# powerblade_3v3.net
KiCad netlist of a schematic drawn in EAGLE
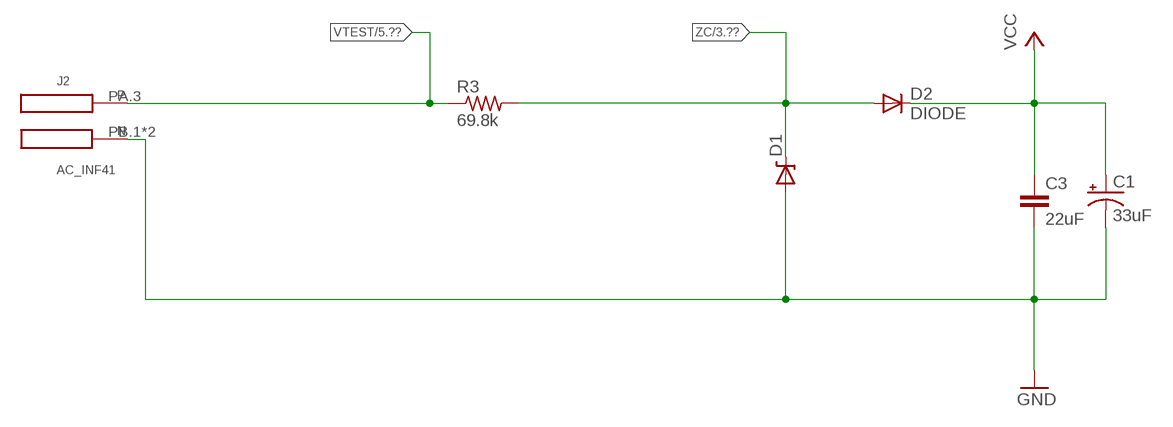
[diagram p0: schematic, sheet 1]
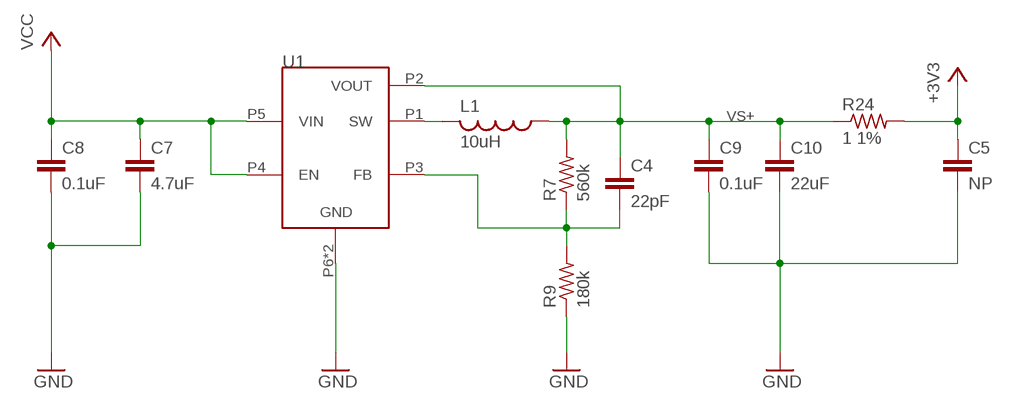
[diagram p1: schematic, sheet 2]
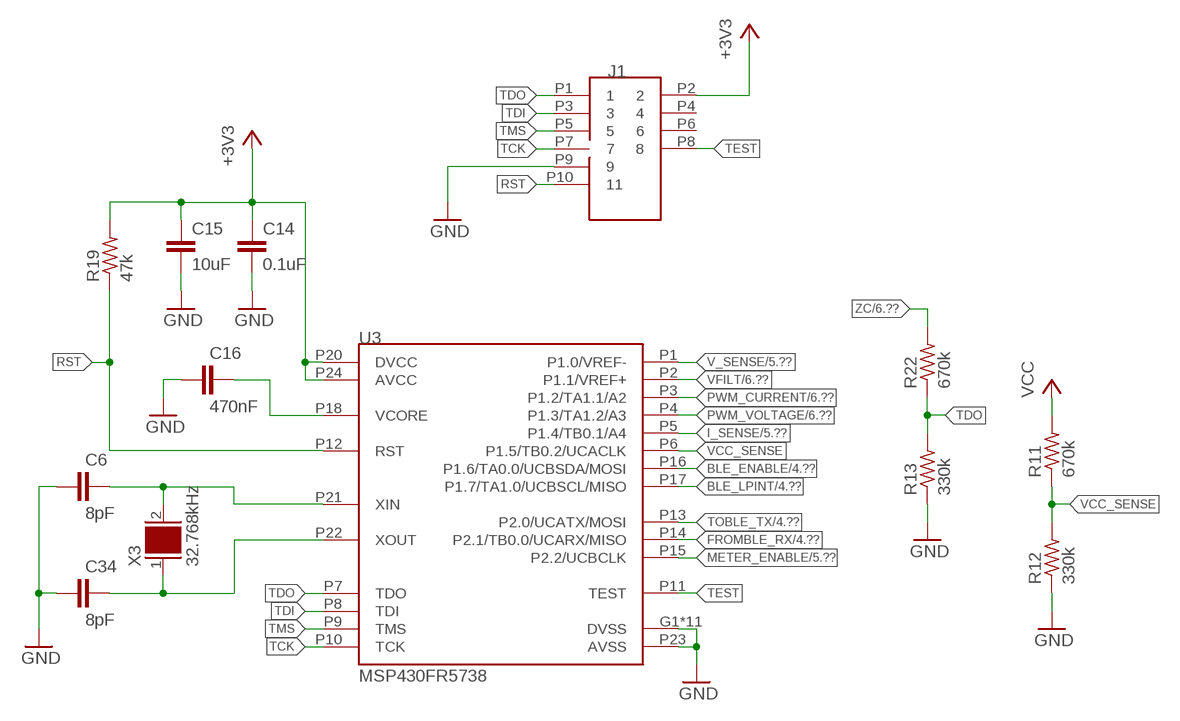
[diagram p2: schematic, sheet 3]
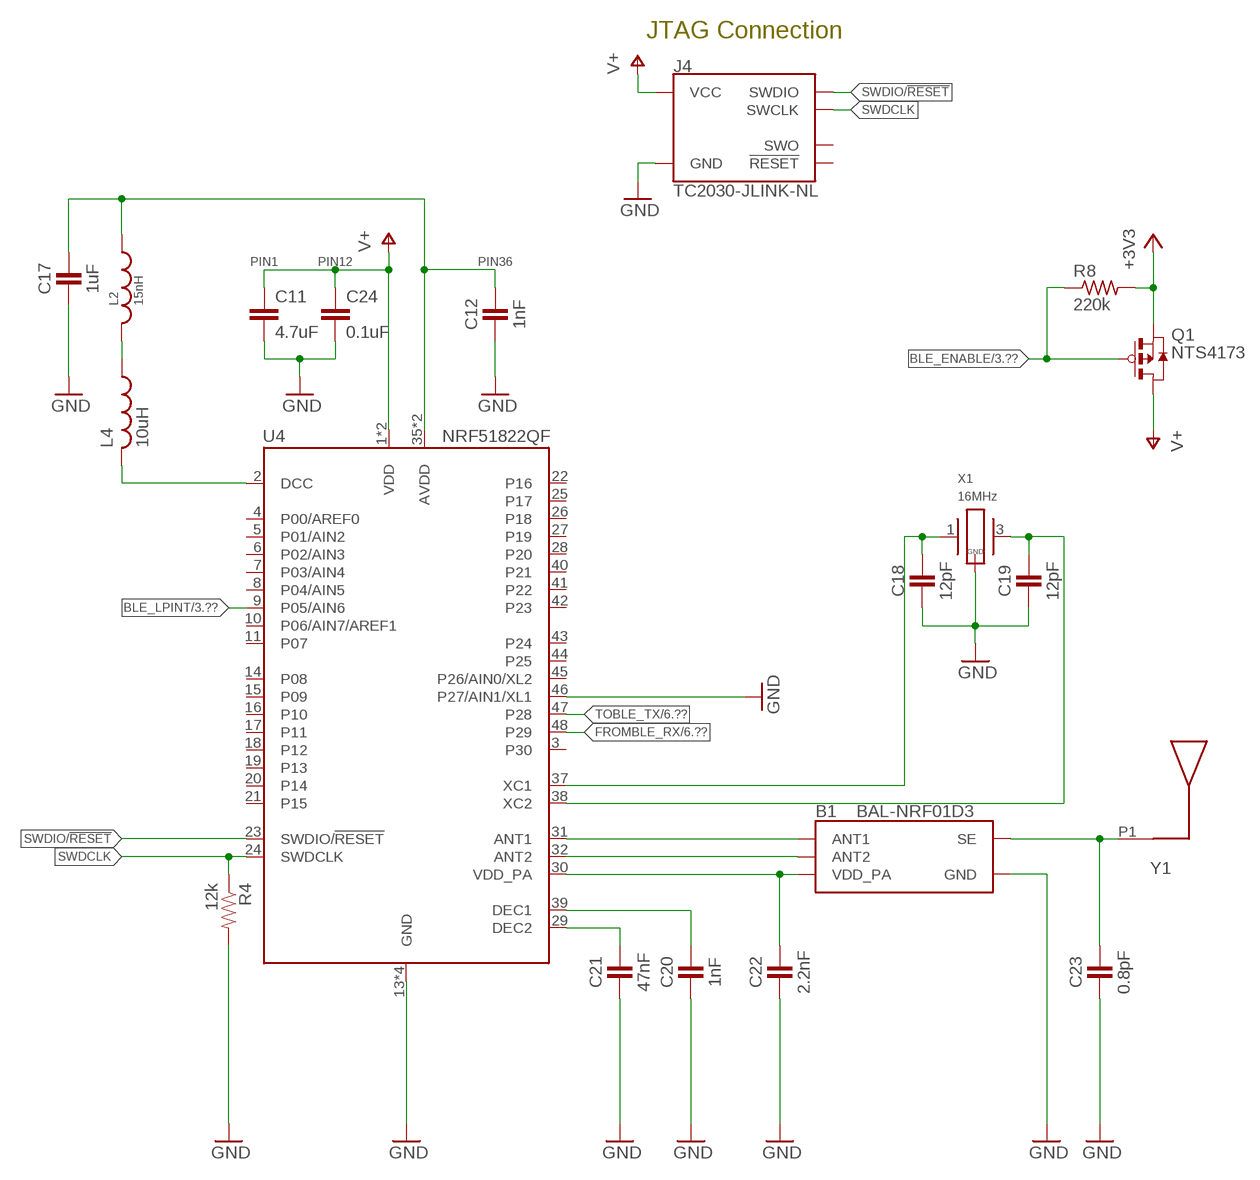
[diagram p3: schematic, sheet 4]
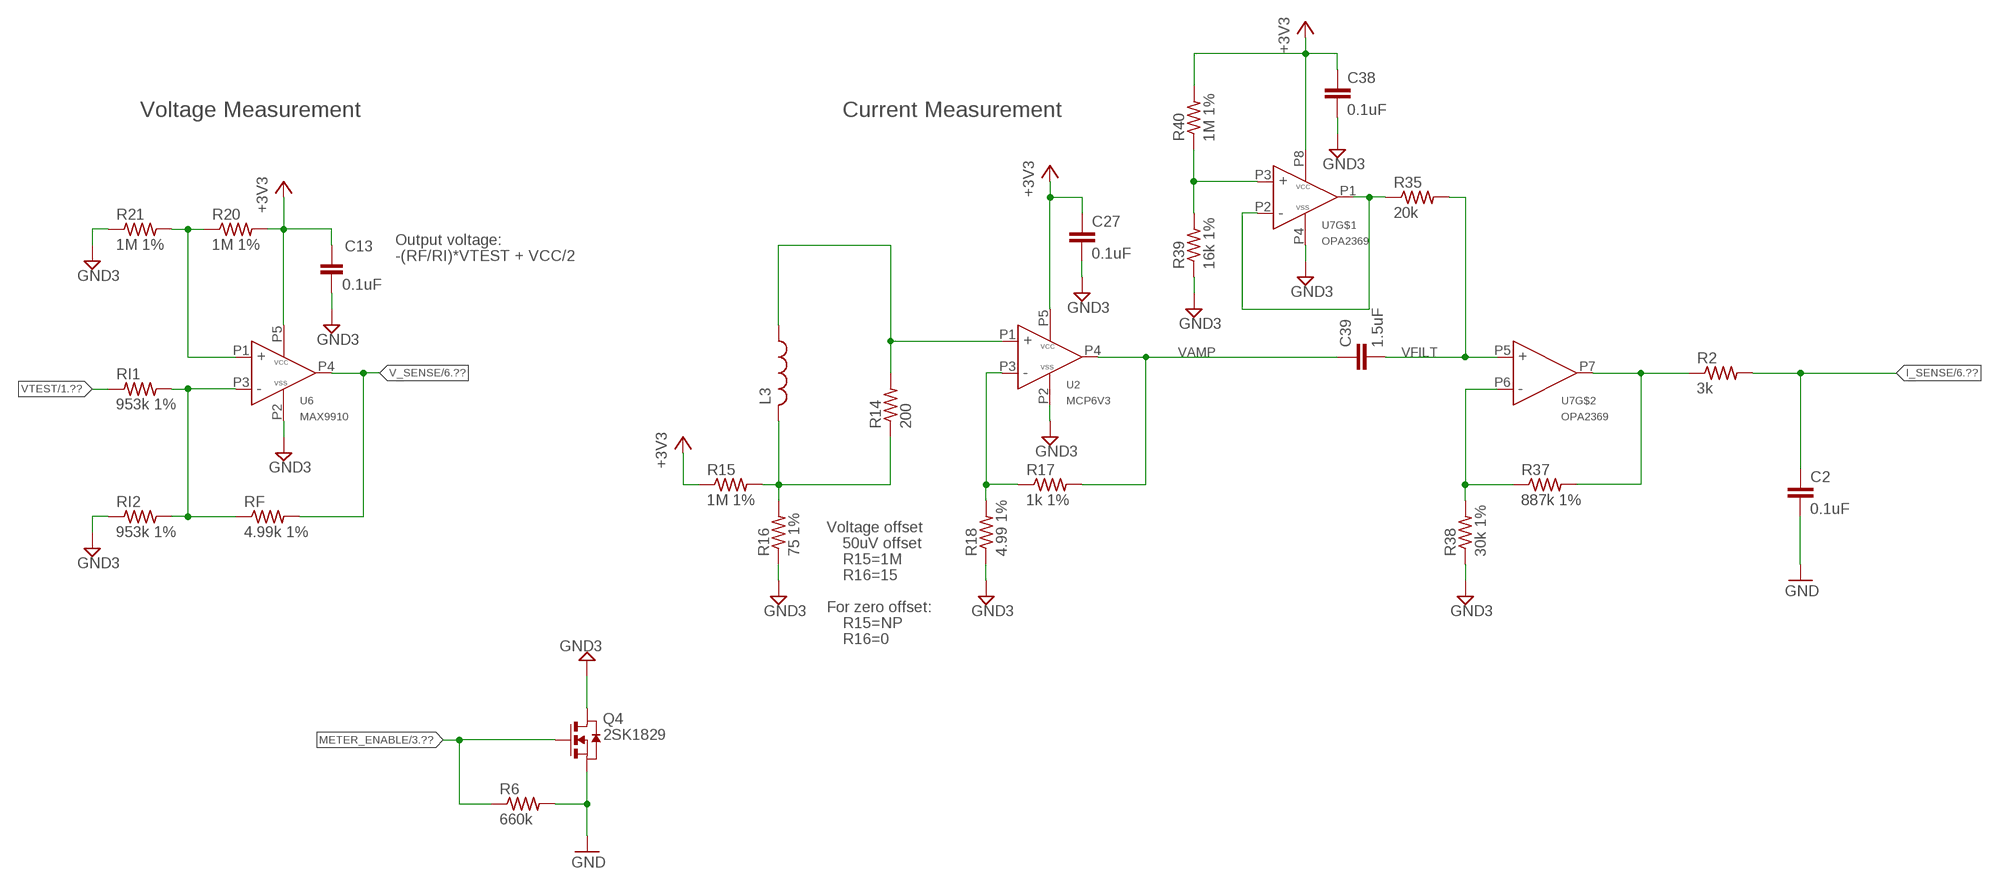
[diagram p4: schematic, sheet 5]
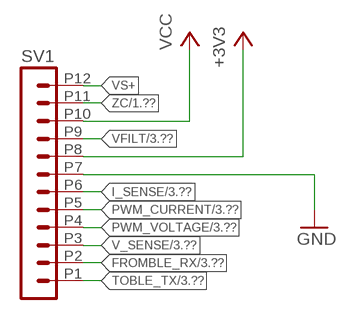
[diagram p5: schematic, sheet 6]

(export (version "E")
  (design (tool "Eeschema 10.0.6"))
  (components
    (comp (ref "C4")
      (value "22pF")
      (footprint "eagle-import:C0402")
      (libsource (lib "eagle-import") (part "C-EUC0402"))
    )
    (comp (ref "C5")
      (value "NP")
      (footprint "eagle-import:C0603_TN")
      (libsource (lib "eagle-import") (part "C-EUC0603_TN"))
    )
    (comp (ref "C7")
      (value "4.7uF")
      (footprint "eagle-import:C0402")
      (libsource (lib "eagle-import") (part "C-EUC0402"))
    )
    (comp (ref "C8")
      (value "0.1uF")
      (footprint "eagle-import:C0402")
      (libsource (lib "eagle-import") (part "C-EUC0402"))
    )
    (comp (ref "C9")
      (value "0.1uF")
      (footprint "eagle-import:C0402_SM")
      (libsource (lib "eagle-import") (part "C-EUC0402_SM"))
    )
    (comp (ref "C10")
      (value "22uF")
      (footprint "eagle-import:C0603_SM")
      (libsource (lib "eagle-import") (part "C-EUC0603_SM"))
    )
    (comp (ref "L1")
      (value "10uH")
      (footprint "eagle-import:L0805")
      (libsource (lib "eagle-import") (part "L-USL0805"))
    )
    (comp (ref "R7")
      (value "560k")
      (footprint "eagle-import:R0402")
      (libsource (lib "eagle-import") (part "R-US_R0402"))
    )
    (comp (ref "R9")
      (value "180k")
      (footprint "eagle-import:R0402")
      (libsource (lib "eagle-import") (part "R-US_R0402"))
    )
    (comp (ref "R24")
      (value "1 1%")
      (footprint "eagle-import:R0603_SM")
      (libsource (lib "eagle-import") (part "R-US_R0603_SM"))
    )
    (comp (ref "U1")
      (value "TPS62122")
      (footprint "eagle-import:WDFN-6")
      (libsource (lib "eagle-import") (part "TPS62122"))
    )
    (comp (ref "C1")
      (value "33uF")
      (footprint "eagle-import:CPOL0805_SM")
      (libsource (lib "eagle-import") (part "CPOL-US0805_SM"))
    )
    (comp (ref "C3")
      (value "22uF")
      (footprint "eagle-import:C0603_SM")
      (libsource (lib "eagle-import") (part "C-EUC0603_SM"))
    )
    (comp (ref "D1")
      (value "ZENERBZT52")
      (footprint "eagle-import:BZT52")
      (fields (field (name "DIGIKEY") "BZT52C10T-7DICT-ND "))
      (libsource (lib "eagle-import") (part "ZENERBZT52"))
    )
    (comp (ref "D2")
      (value "DIODE")
      (footprint "eagle-import:BAS521")
      (libsource (lib "eagle-import") (part "DIODE"))
    )
    (comp (ref "J2")
      (value "AC_INF41")
      (footprint "eagle-import:AC3_F41")
      (libsource (lib "eagle-import") (part "AC_INF41"))
    )
    (comp (ref "R3")
      (value "69.8k")
      (footprint "eagle-import:R1210")
      (libsource (lib "eagle-import") (part "R-US_R1210"))
    )
    (comp (ref "C6")
      (value "8pF")
      (footprint "eagle-import:C0402")
      (libsource (lib "eagle-import") (part "C-EUC0402"))
    )
    (comp (ref "C14")
      (value "0.1uF")
      (footprint "eagle-import:C0402")
      (libsource (lib "eagle-import") (part "C-EUC0402"))
    )
    (comp (ref "C15")
      (value "10uF")
      (footprint "eagle-import:C0603_SM")
      (libsource (lib "eagle-import") (part "C-EUC0603_SM"))
    )
    (comp (ref "C16")
      (value "470nF")
      (footprint "eagle-import:C0402")
      (libsource (lib "eagle-import") (part "C-EUC0402"))
    )
    (comp (ref "C34")
      (value "8pF")
      (footprint "eagle-import:C0402")
      (libsource (lib "eagle-import") (part "C-EUC0402"))
    )
    (comp (ref "J1")
      (value "JTAG_14PIN_IDC-ND")
      (footprint "eagle-import:TC2050-IDC-NL-430-ND")
      (libsource (lib "eagle-import") (part "JTAG_14PIN_IDC-ND"))
    )
    (comp (ref "R11")
      (value "670k")
      (footprint "eagle-import:R0402")
      (libsource (lib "eagle-import") (part "R-US_R0402"))
    )
    (comp (ref "R12")
      (value "330k")
      (footprint "eagle-import:R0402")
      (libsource (lib "eagle-import") (part "R-US_R0402"))
    )
    (comp (ref "R13")
      (value "330k")
      (footprint "eagle-import:R0402")
      (libsource (lib "eagle-import") (part "R-US_R0402"))
    )
    (comp (ref "R19")
      (value "47k")
      (footprint "eagle-import:R0402")
      (libsource (lib "eagle-import") (part "R-US_R0402"))
    )
    (comp (ref "R22")
      (value "670k")
      (footprint "eagle-import:R0402")
      (libsource (lib "eagle-import") (part "R-US_R0402"))
    )
    (comp (ref "U3")
      (value "MSP430FR5738")
      (footprint "eagle-import:VQFN-24")
      (libsource (lib "eagle-import") (part "MSP430FR5738"))
    )
    (comp (ref "X3")
      (value "32.768kHz")
      (footprint "eagle-import:0805")
      (libsource (lib "eagle-import") (part "CRYSTAL_0805"))
    )
    (comp (ref "B1")
      (value "BAL-NRF01D3")
      (footprint "eagle-import:BAL-NRF01D3")
      (libsource (lib "eagle-import") (part "BAL-NRF01D3"))
    )
    (comp (ref "C11")
      (value "4.7uF")
      (footprint "eagle-import:C0402")
      (libsource (lib "eagle-import") (part "C-EUC0402"))
    )
    (comp (ref "C12")
      (value "1nF")
      (footprint "eagle-import:0402_CAP")
      (libsource (lib "eagle-import") (part "CAPACITOR"))
    )
    (comp (ref "C17")
      (value "1uF")
      (footprint "eagle-import:0402_CAP")
      (libsource (lib "eagle-import") (part "CAPACITOR"))
    )
    (comp (ref "C18")
      (value "12pF")
      (footprint "eagle-import:0402_CAP")
      (libsource (lib "eagle-import") (part "CAPACITOR"))
    )
    (comp (ref "C19")
      (value "12pF")
      (footprint "eagle-import:0402_CAP")
      (libsource (lib "eagle-import") (part "CAPACITOR"))
    )
    (comp (ref "C20")
      (value "1nF")
      (footprint "eagle-import:0402_CAP")
      (libsource (lib "eagle-import") (part "CAPACITOR"))
    )
    (comp (ref "C21")
      (value "47nF")
      (footprint "eagle-import:0402_CAP")
      (libsource (lib "eagle-import") (part "CAPACITOR"))
    )
    (comp (ref "C22")
      (value "2.2nF")
      (footprint "eagle-import:0402_CAP")
      (libsource (lib "eagle-import") (part "CAPACITOR"))
    )
    (comp (ref "C23")
      (value "0.8pF")
      (footprint "eagle-import:0402_CAP")
      (libsource (lib "eagle-import") (part "CAPACITOR"))
    )
    (comp (ref "C24")
      (value "0.1uF")
      (footprint "eagle-import:C0402")
      (libsource (lib "eagle-import") (part "C-EUC0402"))
    )
    (comp (ref "J4")
      (value "TC2030-JLINK-NL")
      (footprint "eagle-import:TC2030-IDC-NL")
      (libsource (lib "eagle-import") (part "TC2030-JLINK-NL"))
    )
    (comp (ref "L2")
      (value "15nH")
      (footprint "eagle-import:0402_CAP")
      (libsource (lib "eagle-import") (part "INDUCTOR0402"))
    )
    (comp (ref "L4")
      (value "10uH")
      (footprint "eagle-import:C0603_TN")
      (libsource (lib "eagle-import") (part "L-USL0603_TN"))
    )
    (comp (ref "Q1")
      (value "NTS4173")
      (footprint "eagle-import:SC-70-3")
      (libsource (lib "eagle-import") (part "NTS4173"))
    )
    (comp (ref "R4")
      (value "12k")
      (footprint "eagle-import:0402_RES")
      (libsource (lib "eagle-import") (part "RESISTOR"))
    )
    (comp (ref "R8")
      (value "220k")
      (footprint "eagle-import:R0402_SM")
      (libsource (lib "eagle-import") (part "R-US_R0402_SM"))
    )
    (comp (ref "U4")
      (value "NRF51822QF")
      (footprint "eagle-import:QFN-48-6MM")
      (libsource (lib "eagle-import") (part "NRF51822QF"))
    )
    (comp (ref "X1")
      (value "16MHz")
      (footprint "eagle-import:TXC-8Y")
      (libsource (lib "eagle-import") (part "TXC-8Y"))
    )
    (comp (ref "Y1")
      (value "UREACH_XTEND")
      (footprint "eagle-import:UREACH_XTEND")
      (libsource (lib "eagle-import") (part "UREACH_XTEND"))
    )
    (comp (ref "C2")
      (value "0.1uF")
      (footprint "eagle-import:C0402")
      (libsource (lib "eagle-import") (part "C-EUC0402"))
    )
    (comp (ref "C13")
      (value "0.1uF")
      (footprint "eagle-import:0402_CAP")
      (libsource (lib "eagle-import") (part "CAPACITOR"))
    )
    (comp (ref "C27")
      (value "0.1uF")
      (footprint "eagle-import:C0402")
      (libsource (lib "eagle-import") (part "C-EUC0402"))
    )
    (comp (ref "C38")
      (value "0.1uF")
      (footprint "eagle-import:C0402")
      (libsource (lib "eagle-import") (part "C-EUC0402"))
    )
    (comp (ref "C39")
      (value "1.5uF")
      (footprint "eagle-import:C0402")
      (libsource (lib "eagle-import") (part "C-EUC0402"))
    )
    (comp (ref "L3")
      (value "L-USL0805")
      (footprint "eagle-import:L0805")
      (libsource (lib "eagle-import") (part "L-USL0805"))
    )
    (comp (ref "Q4")
      (value "2SK1829")
      (footprint "eagle-import:SC-70-3")
      (libsource (lib "eagle-import") (part "2SK1829"))
    )
    (comp (ref "R2")
      (value "3k")
      (footprint "eagle-import:R0402_SM")
      (libsource (lib "eagle-import") (part "R-US_R0402_SM"))
    )
    (comp (ref "R6")
      (value "660k")
      (footprint "eagle-import:R0402")
      (libsource (lib "eagle-import") (part "R-US_R0402"))
    )
    (comp (ref "R14")
      (value "200")
      (footprint "eagle-import:R0402")
      (libsource (lib "eagle-import") (part "R-US_R0402"))
    )
    (comp (ref "R15")
      (value "1M 1%")
      (footprint "eagle-import:R0402")
      (libsource (lib "eagle-import") (part "R-US_R0402"))
    )
    (comp (ref "R16")
      (value "75 1%")
      (footprint "eagle-import:R0402")
      (libsource (lib "eagle-import") (part "R-US_R0402"))
    )
    (comp (ref "R17")
      (value "1k 1%")
      (footprint "eagle-import:R0402")
      (libsource (lib "eagle-import") (part "R-US_R0402"))
    )
    (comp (ref "R18")
      (value "4.99 1%")
      (footprint "eagle-import:R0402")
      (libsource (lib "eagle-import") (part "R-US_R0402"))
    )
    (comp (ref "R20")
      (value "1M 1%")
      (footprint "eagle-import:R0402")
      (libsource (lib "eagle-import") (part "R-US_R0402"))
    )
    (comp (ref "R21")
      (value "1M 1%")
      (footprint "eagle-import:R0402_SM")
      (libsource (lib "eagle-import") (part "R-US_R0402_SM"))
    )
    (comp (ref "R35")
      (value "20k")
      (footprint "eagle-import:R0402")
      (libsource (lib "eagle-import") (part "R-US_R0402"))
    )
    (comp (ref "R37")
      (value "887k 1%")
      (footprint "eagle-import:R0402")
      (libsource (lib "eagle-import") (part "R-US_R0402"))
    )
    (comp (ref "R38")
      (value "30k 1%")
      (footprint "eagle-import:R0402")
      (libsource (lib "eagle-import") (part "R-US_R0402"))
    )
    (comp (ref "R39")
      (value "16k 1%")
      (footprint "eagle-import:R0402")
      (libsource (lib "eagle-import") (part "R-US_R0402"))
    )
    (comp (ref "R40")
      (value "1M 1%")
      (footprint "eagle-import:R0402")
      (libsource (lib "eagle-import") (part "R-US_R0402"))
    )
    (comp (ref "RF")
      (value "4.99k 1%")
      (footprint "eagle-import:R0402")
      (libsource (lib "eagle-import") (part "R-US_R0402"))
    )
    (comp (ref "RI1")
      (value "953k 1%")
      (footprint "eagle-import:R0402")
      (libsource (lib "eagle-import") (part "R-US_R0402"))
    )
    (comp (ref "RI2")
      (value "953k 1%")
      (footprint "eagle-import:R0402")
      (libsource (lib "eagle-import") (part "R-US_R0402"))
    )
    (comp (ref "U2")
      (value "MCP6V3")
      (footprint "eagle-import:SC70-5")
      (fields (field (name "DIGIKEY") "296-19547-1-ND"))
      (libsource (lib "eagle-import") (part "MCP6V3"))
    )
    (comp (ref "U6")
      (value "MAX9910")
      (footprint "eagle-import:SC70-5")
      (fields (field (name "DIGIKEY") "296-25252-1-ND"))
      (libsource (lib "eagle-import") (part "MAX9910"))
    )
    (comp (ref "U7")
      (value "OPA2369")
      (footprint "eagle-import:SOT-23-8")
      (libsource (lib "eagle-import") (part "OPA2369"))
    )
    (comp (ref "SV1")
      (value "MA12-11M27")
      (footprint "eagle-import:MA12-1_1MM27")
      (libsource (lib "eagle-import") (part "MA12-11M27"))
    )
  )
  (nets
    (net (code "1") (name "+3V3") (class "Default")
      (node (ref "C13") (pin "1") (pinfunction "1_1") (pintype "bidirectional"))
      (node (ref "C14") (pin "1") (pinfunction "1_1") (pintype "passive"))
      (node (ref "C15") (pin "1") (pinfunction "1_1") (pintype "passive"))
      (node (ref "C27") (pin "1") (pinfunction "1_1") (pintype "passive"))
      (node (ref "C38") (pin "1") (pinfunction "1_1") (pintype "passive"))
      (node (ref "C5") (pin "1") (pinfunction "1_1") (pintype "passive"))
      (node (ref "J1") (pin "P2") (pinfunction "2_P2") (pintype "bidirectional"))
      (node (ref "Q1") (pin "P2") (pinfunction "S_P2") (pintype "passive"))
      (node (ref "R15") (pin "1") (pinfunction "1_1") (pintype "passive"))
      (node (ref "R19") (pin "2") (pinfunction "2_2") (pintype "passive"))
      (node (ref "R20") (pin "2") (pinfunction "2_2") (pintype "passive"))
      (node (ref "R24") (pin "2") (pinfunction "2_2") (pintype "passive"))
      (node (ref "R40") (pin "2") (pinfunction "2_2") (pintype "passive"))
      (node (ref "R8") (pin "2") (pinfunction "2_2") (pintype "passive"))
      (node (ref "SV1") (pin "P8") (pinfunction "8_P8") (pintype "passive"))
      (node (ref "U2") (pin "P5") (pinfunction "VCC_P5") (pintype "bidirectional"))
      (node (ref "U3") (pin "P20") (pinfunction "DVCC_P20") (pintype "bidirectional"))
      (node (ref "U3") (pin "P24") (pinfunction "AVCC_P24") (pintype "bidirectional"))
      (node (ref "U6") (pin "P5") (pinfunction "VCC_P5") (pintype "bidirectional"))
      (node (ref "U7") (pin "P8") (pinfunction "VCC_P8") (pintype "bidirectional"))
    )
    (net (code "2") (name "BLE_ENABLE") (class "Default")
      (node (ref "Q1") (pin "P1") (pinfunction "G_P1") (pintype "passive"))
      (node (ref "R8") (pin "1") (pinfunction "1_1") (pintype "passive"))
      (node (ref "U3") (pin "P16") (pinfunction "P1.6/TA0.0/UCBSDA/MOSI_P16") (pintype "bidirectional"))
    )
    (net (code "3") (name "BLE_LPINT") (class "Default")
      (node (ref "U3") (pin "P17") (pinfunction "P1.7/TA1.0/UCBSCL/MISO_P17") (pintype "bidirectional"))
      (node (ref "U4") (pin "9") (pinfunction "P05/AIN6_9") (pintype "bidirectional"))
    )
    (net (code "4") (name "FROMBLE_RX") (class "Default")
      (node (ref "SV1") (pin "P2") (pinfunction "2_P2") (pintype "passive"))
      (node (ref "U3") (pin "P14") (pinfunction "P2.1/TB0.0/UCARX/MISO_P14") (pintype "bidirectional"))
      (node (ref "U4") (pin "48") (pinfunction "P29_48") (pintype "bidirectional"))
    )
    (net (code "5") (name "GND") (class "Default")
      (node (ref "B1") (pin "GND") (pinfunction "GND_GND") (pintype "bidirectional"))
      (node (ref "C1") (pin "-") (pinfunction "-_-") (pintype "passive"))
      (node (ref "C10") (pin "2") (pinfunction "2_2") (pintype "passive"))
      (node (ref "C11") (pin "2") (pinfunction "2_2") (pintype "passive"))
      (node (ref "C12") (pin "2") (pinfunction "2_2") (pintype "bidirectional"))
      (node (ref "C14") (pin "2") (pinfunction "2_2") (pintype "passive"))
      (node (ref "C15") (pin "2") (pinfunction "2_2") (pintype "passive"))
      (node (ref "C16") (pin "1") (pinfunction "1_1") (pintype "passive"))
      (node (ref "C17") (pin "2") (pinfunction "2_2") (pintype "bidirectional"))
      (node (ref "C18") (pin "2") (pinfunction "2_2") (pintype "bidirectional"))
      (node (ref "C19") (pin "2") (pinfunction "2_2") (pintype "bidirectional"))
      (node (ref "C2") (pin "2") (pinfunction "2_2") (pintype "passive"))
      (node (ref "C20") (pin "2") (pinfunction "2_2") (pintype "bidirectional"))
      (node (ref "C21") (pin "2") (pinfunction "2_2") (pintype "bidirectional"))
      (node (ref "C22") (pin "2") (pinfunction "2_2") (pintype "bidirectional"))
      (node (ref "C23") (pin "2") (pinfunction "2_2") (pintype "bidirectional"))
      (node (ref "C24") (pin "2") (pinfunction "2_2") (pintype "passive"))
      (node (ref "C3") (pin "2") (pinfunction "2_2") (pintype "passive"))
      (node (ref "C34") (pin "1") (pinfunction "1_1") (pintype "passive"))
      (node (ref "C5") (pin "2") (pinfunction "2_2") (pintype "passive"))
      (node (ref "C6") (pin "1") (pinfunction "1_1") (pintype "passive"))
      (node (ref "C7") (pin "2") (pinfunction "2_2") (pintype "passive"))
      (node (ref "C8") (pin "2") (pinfunction "2_2") (pintype "passive"))
      (node (ref "C9") (pin "2") (pinfunction "2_2") (pintype "passive"))
      (node (ref "D1") (pin "A") (pinfunction "A_A") (pintype "passive"))
      (node (ref "J1") (pin "P9") (pinfunction "9_P9") (pintype "bidirectional"))
      (node (ref "J2") (pin "PB.1") (pinfunction "N_PB.1") (pintype "bidirectional"))
      (node (ref "J2") (pin "PB.3") (pinfunction "N_PB.3") (pintype "bidirectional"))
      (node (ref "J4") (pin "5") (pinfunction "GND_5") (pintype "bidirectional"))
      (node (ref "Q4") (pin "P2") (pinfunction "S_P2") (pintype "passive"))
      (node (ref "R12") (pin "1") (pinfunction "1_1") (pintype "passive"))
      (node (ref "R13") (pin "1") (pinfunction "1_1") (pintype "passive"))
      (node (ref "R4") (pin "2") (pinfunction "2_2") (pintype "passive"))
      (node (ref "R6") (pin "2") (pinfunction "2_2") (pintype "passive"))
      (node (ref "R9") (pin "1") (pinfunction "1_1") (pintype "passive"))
      (node (ref "SV1") (pin "P7") (pinfunction "7_P7") (pintype "passive"))
      (node (ref "U1") (pin "P6") (pinfunction "GND_P6") (pintype "bidirectional"))
      (node (ref "U1") (pin "PAD") (pinfunction "GND_PAD") (pintype "bidirectional"))
      (node (ref "U3") (pin "G1") (pinfunction "DVSS_G1") (pintype "bidirectional"))
      (node (ref "U3") (pin "G2") (pinfunction "DVSS_G2") (pintype "bidirectional"))
      (node (ref "U3") (pin "G3") (pinfunction "DVSS_G3") (pintype "bidirectional"))
      (node (ref "U3") (pin "G4") (pinfunction "DVSS_G4") (pintype "bidirectional"))
      (node (ref "U3") (pin "G5") (pinfunction "DVSS_G5") (pintype "bidirectional"))
      (node (ref "U3") (pin "G6") (pinfunction "DVSS_G6") (pintype "bidirectional"))
      (node (ref "U3") (pin "G7") (pinfunction "DVSS_G7") (pintype "bidirectional"))
      (node (ref "U3") (pin "G8") (pinfunction "DVSS_G8") (pintype "bidirectional"))
      (node (ref "U3") (pin "G9") (pinfunction "DVSS_G9") (pintype "bidirectional"))
      (node (ref "U3") (pin "P19") (pinfunction "DVSS_P19") (pintype "bidirectional"))
      (node (ref "U3") (pin "P23") (pinfunction "AVSS_P23") (pintype "bidirectional"))
      (node (ref "U3") (pin "PAD") (pinfunction "DVSS_PAD") (pintype "bidirectional"))
      (node (ref "U4") (pin "13") (pinfunction "GND_13") (pintype "bidirectional"))
      (node (ref "U4") (pin "33") (pinfunction "GND_33") (pintype "bidirectional"))
      (node (ref "U4") (pin "34") (pinfunction "GND_34") (pintype "bidirectional"))
      (node (ref "U4") (pin "46") (pinfunction "P27/AIN1/XL1_46") (pintype "bidirectional"))
      (node (ref "U4") (pin "GND") (pinfunction "GND_GND") (pintype "bidirectional"))
      (node (ref "X1") (pin "2") (pinfunction "GND_2") (pintype "bidirectional"))
      (node (ref "X1") (pin "4") (pinfunction "GND_4") (pintype "bidirectional"))
    )
    (net (code "6") (name "GND3") (class "Default")
      (node (ref "C13") (pin "2") (pinfunction "2_2") (pintype "bidirectional"))
      (node (ref "C27") (pin "2") (pinfunction "2_2") (pintype "passive"))
      (node (ref "C38") (pin "2") (pinfunction "2_2") (pintype "passive"))
      (node (ref "Q4") (pin "P3") (pinfunction "D_P3") (pintype "passive"))
      (node (ref "R16") (pin "1") (pinfunction "1_1") (pintype "passive"))
      (node (ref "R18") (pin "1") (pinfunction "1_1") (pintype "passive"))
      (node (ref "R21") (pin "1") (pinfunction "1_1") (pintype "passive"))
      (node (ref "R38") (pin "1") (pinfunction "1_1") (pintype "passive"))
      (node (ref "R39") (pin "1") (pinfunction "1_1") (pintype "passive"))
      (node (ref "RI2") (pin "1") (pinfunction "1_1") (pintype "passive"))
      (node (ref "U2") (pin "P2") (pinfunction "VSS_P2") (pintype "bidirectional"))
      (node (ref "U6") (pin "P2") (pinfunction "VSS_P2") (pintype "bidirectional"))
      (node (ref "U7") (pin "P4") (pinfunction "VSS_P4") (pintype "bidirectional"))
    )
    (net (code "7") (name "I_SENSE") (class "Default")
      (node (ref "C2") (pin "1") (pinfunction "1_1") (pintype "passive"))
      (node (ref "R2") (pin "2") (pinfunction "2_2") (pintype "passive"))
      (node (ref "SV1") (pin "P6") (pinfunction "6_P6") (pintype "passive"))
      (node (ref "U3") (pin "P5") (pinfunction "P1.4/TB0.1/A4_P5") (pintype "bidirectional"))
    )
    (net (code "8") (name "METER_ENABLE") (class "Default")
      (node (ref "Q4") (pin "P1") (pinfunction "G_P1") (pintype "passive"))
      (node (ref "R6") (pin "1") (pinfunction "1_1") (pintype "passive"))
      (node (ref "U3") (pin "P15") (pinfunction "P2.2/UCBCLK_P15") (pintype "bidirectional"))
    )
    (net (code "9") (name "Net-(B1-PadSE)") (class "Default")
      (node (ref "B1") (pin "SE") (pinfunction "SE_SE") (pintype "bidirectional"))
      (node (ref "C23") (pin "1") (pinfunction "1_1") (pintype "bidirectional"))
      (node (ref "Y1") (pin "P1") (pinfunction "P1_P1") (pintype "bidirectional"))
    )
    (net (code "10") (name "Net-(B1-VDD_PA)") (class "Default")
      (node (ref "B1") (pin "VCC") (pinfunction "VDD_PA_VCC") (pintype "bidirectional"))
      (node (ref "C22") (pin "1") (pinfunction "1_1") (pintype "bidirectional"))
      (node (ref "U4") (pin "30") (pinfunction "VDD_PA_30") (pintype "bidirectional"))
    )
    (net (code "11") (name "Net-(C12-Pad1)") (class "Default")
      (node (ref "C12") (pin "1") (pinfunction "1_1") (pintype "bidirectional"))
      (node (ref "C17") (pin "1") (pinfunction "1_1") (pintype "bidirectional"))
      (node (ref "L2") (pin "1") (pinfunction "1_1") (pintype "bidirectional"))
      (node (ref "U4") (pin "35") (pinfunction "AVDD_35") (pintype "bidirectional"))
      (node (ref "U4") (pin "36") (pinfunction "AVDD_36") (pintype "bidirectional"))
    )
    (net (code "12") (name "Net-(L2-Pad2)") (class "Default")
      (node (ref "L2") (pin "2") (pinfunction "2_2") (pintype "bidirectional"))
      (node (ref "L4") (pin "1") (pinfunction "1_1") (pintype "passive"))
    )
    (net (code "13") (name "Net-(L3-Pad2)") (class "Default")
      (node (ref "L3") (pin "2") (pinfunction "2_2") (pintype "passive"))
      (node (ref "R14") (pin "1") (pinfunction "1_1") (pintype "passive"))
      (node (ref "R15") (pin "2") (pinfunction "2_2") (pintype "passive"))
      (node (ref "R16") (pin "2") (pinfunction "2_2") (pintype "passive"))
    )
    (net (code "14") (name "Net-(U1-FB)") (class "Default")
      (node (ref "C4") (pin "2") (pinfunction "2_2") (pintype "passive"))
      (node (ref "R7") (pin "1") (pinfunction "1_1") (pintype "passive"))
      (node (ref "R9") (pin "2") (pinfunction "2_2") (pintype "passive"))
      (node (ref "U1") (pin "P3") (pinfunction "FB_P3") (pintype "bidirectional"))
    )
    (net (code "15") (name "Net-(U1-SW)") (class "Default")
      (node (ref "L1") (pin "2") (pinfunction "2_2") (pintype "passive"))
      (node (ref "U1") (pin "P1") (pinfunction "SW_P1") (pintype "bidirectional"))
    )
    (net (code "16") (name "Net-(U2-IN+)") (class "Default")
      (node (ref "L3") (pin "1") (pinfunction "1_1") (pintype "passive"))
      (node (ref "R14") (pin "2") (pinfunction "2_2") (pintype "passive"))
      (node (ref "U2") (pin "P1") (pinfunction "IN+_P1") (pintype "bidirectional"))
    )
    (net (code "17") (name "Net-(U2-IN-)") (class "Default")
      (node (ref "R17") (pin "1") (pinfunction "1_1") (pintype "passive"))
      (node (ref "R18") (pin "2") (pinfunction "2_2") (pintype "passive"))
      (node (ref "U2") (pin "P3") (pinfunction "IN-_P3") (pintype "bidirectional"))
    )
    (net (code "18") (name "Net-(U3-VCORE)") (class "Default")
      (node (ref "C16") (pin "2") (pinfunction "2_2") (pintype "passive"))
      (node (ref "U3") (pin "P18") (pinfunction "VCORE_P18") (pintype "bidirectional"))
    )
    (net (code "19") (name "Net-(U3-XIN)") (class "Default")
      (node (ref "C6") (pin "2") (pinfunction "2_2") (pintype "passive"))
      (node (ref "U3") (pin "P21") (pinfunction "XIN_P21") (pintype "bidirectional"))
      (node (ref "X3") (pin "2") (pinfunction "P2_2") (pintype "bidirectional"))
    )
    (net (code "20") (name "Net-(U3-XOUT)") (class "Default")
      (node (ref "C34") (pin "2") (pinfunction "2_2") (pintype "passive"))
      (node (ref "U3") (pin "P22") (pinfunction "XOUT_P22") (pintype "bidirectional"))
      (node (ref "X3") (pin "1") (pinfunction "P1_1") (pintype "bidirectional"))
    )
    (net (code "21") (name "Net-(U4-ANT1)") (class "Default")
      (node (ref "B1") (pin "ANT1") (pinfunction "ANT1_ANT1") (pintype "bidirectional"))
      (node (ref "U4") (pin "31") (pinfunction "ANT1_31") (pintype "bidirectional"))
    )
    (net (code "22") (name "Net-(U4-ANT2)") (class "Default")
      (node (ref "B1") (pin "ANT2") (pinfunction "ANT2_ANT2") (pintype "bidirectional"))
      (node (ref "U4") (pin "32") (pinfunction "ANT2_32") (pintype "bidirectional"))
    )
    (net (code "23") (name "Net-(U4-DCC)") (class "Default")
      (node (ref "L4") (pin "2") (pinfunction "2_2") (pintype "passive"))
      (node (ref "U4") (pin "2") (pinfunction "DCC_2") (pintype "bidirectional"))
    )
    (net (code "24") (name "Net-(U4-DEC1)") (class "Default")
      (node (ref "C20") (pin "1") (pinfunction "1_1") (pintype "bidirectional"))
      (node (ref "U4") (pin "39") (pinfunction "DEC1_39") (pintype "bidirectional"))
    )
    (net (code "25") (name "Net-(U4-DEC2)") (class "Default")
      (node (ref "C21") (pin "1") (pinfunction "1_1") (pintype "bidirectional"))
      (node (ref "U4") (pin "29") (pinfunction "DEC2_29") (pintype "bidirectional"))
    )
    (net (code "26") (name "Net-(U4-XC1)") (class "Default")
      (node (ref "C18") (pin "1") (pinfunction "1_1") (pintype "bidirectional"))
      (node (ref "U4") (pin "37") (pinfunction "XC1_37") (pintype "bidirectional"))
      (node (ref "X1") (pin "1") (pinfunction "1_1") (pintype "bidirectional"))
    )
    (net (code "27") (name "Net-(U4-XC2)") (class "Default")
      (node (ref "C19") (pin "1") (pinfunction "1_1") (pintype "bidirectional"))
      (node (ref "U4") (pin "38") (pinfunction "XC2_38") (pintype "bidirectional"))
      (node (ref "X1") (pin "3") (pinfunction "2_3") (pintype "bidirectional"))
    )
    (net (code "28") (name "Net-(U6-IN+)") (class "Default")
      (node (ref "R20") (pin "1") (pinfunction "1_1") (pintype "passive"))
      (node (ref "R21") (pin "2") (pinfunction "2_2") (pintype "passive"))
      (node (ref "U6") (pin "P1") (pinfunction "IN+_P1") (pintype "bidirectional"))
    )
    (net (code "29") (name "Net-(U6-IN-)") (class "Default")
      (node (ref "RF") (pin "1") (pinfunction "1_1") (pintype "passive"))
      (node (ref "RI1") (pin "2") (pinfunction "2_2") (pintype "passive"))
      (node (ref "RI2") (pin "2") (pinfunction "2_2") (pintype "passive"))
      (node (ref "U6") (pin "P3") (pinfunction "IN-_P3") (pintype "bidirectional"))
    )
    (net (code "30") (name "Net-(U7A-IN+)") (class "Default")
      (node (ref "R39") (pin "2") (pinfunction "2_2") (pintype "passive"))
      (node (ref "R40") (pin "1") (pinfunction "1_1") (pintype "passive"))
      (node (ref "U7") (pin "P3") (pinfunction "IN+_P3") (pintype "bidirectional"))
    )
    (net (code "31") (name "Net-(U7A-IN-)") (class "Default")
      (node (ref "R35") (pin "1") (pinfunction "1_1") (pintype "passive"))
      (node (ref "U7") (pin "P1") (pinfunction "OUT_P1") (pintype "bidirectional"))
      (node (ref "U7") (pin "P2") (pinfunction "IN-_P2") (pintype "bidirectional"))
    )
    (net (code "32") (name "Net-(U7B-IN-)") (class "Default")
      (node (ref "R37") (pin "1") (pinfunction "1_1") (pintype "passive"))
      (node (ref "R38") (pin "2") (pinfunction "2_2") (pintype "passive"))
      (node (ref "U7") (pin "P6") (pinfunction "IN-_P6") (pintype "bidirectional"))
    )
    (net (code "33") (name "Net-(U7B-OUT)") (class "Default")
      (node (ref "R2") (pin "1") (pinfunction "1_1") (pintype "passive"))
      (node (ref "R37") (pin "2") (pinfunction "2_2") (pintype "passive"))
      (node (ref "U7") (pin "P7") (pinfunction "OUT_P7") (pintype "bidirectional"))
    )
    (net (code "34") (name "PWM_CURRENT") (class "Default")
      (node (ref "SV1") (pin "P5") (pinfunction "5_P5") (pintype "passive"))
      (node (ref "U3") (pin "P3") (pinfunction "P1.2/TA1.1/A2_P3") (pintype "bidirectional"))
    )
    (net (code "35") (name "PWM_VOLTAGE") (class "Default")
      (node (ref "SV1") (pin "P4") (pinfunction "4_P4") (pintype "passive"))
      (node (ref "U3") (pin "P4") (pinfunction "P1.3/TA1.2/A3_P4") (pintype "bidirectional"))
    )
    (net (code "36") (name "RST") (class "Default")
      (node (ref "J1") (pin "P10") (pinfunction "11_P10") (pintype "bidirectional"))
      (node (ref "R19") (pin "1") (pinfunction "1_1") (pintype "passive"))
      (node (ref "U3") (pin "P12") (pinfunction "RST_P12") (pintype "bidirectional"))
    )
    (net (code "37") (name "SWDCLK") (class "Default")
      (node (ref "J4") (pin "4") (pinfunction "SWCLK_4") (pintype "bidirectional"))
      (node (ref "R4") (pin "1") (pinfunction "1_1") (pintype "passive"))
      (node (ref "U4") (pin "24") (pinfunction "SWDCLK_24") (pintype "bidirectional"))
    )
    (net (code "38") (name "SWDIO{slash}~{RESET}") (class "Default")
      (node (ref "J4") (pin "2") (pinfunction "SWDIO_2") (pintype "bidirectional"))
      (node (ref "U4") (pin "23") (pinfunction "SWDIO/~{RESET}_23") (pintype "bidirectional"))
    )
    (net (code "39") (name "TCK") (class "Default")
      (node (ref "J1") (pin "P7") (pinfunction "7_P7") (pintype "bidirectional"))
      (node (ref "U3") (pin "P10") (pinfunction "TCK_P10") (pintype "bidirectional"))
    )
    (net (code "40") (name "TDI") (class "Default")
      (node (ref "J1") (pin "P3") (pinfunction "3_P3") (pintype "bidirectional"))
      (node (ref "U3") (pin "P8") (pinfunction "TDI_P8") (pintype "bidirectional"))
    )
    (net (code "41") (name "TDO") (class "Default")
      (node (ref "J1") (pin "P1") (pinfunction "1_P1") (pintype "bidirectional"))
      (node (ref "R13") (pin "2") (pinfunction "2_2") (pintype "passive"))
      (node (ref "R22") (pin "1") (pinfunction "1_1") (pintype "passive"))
      (node (ref "U3") (pin "P7") (pinfunction "TDO_P7") (pintype "bidirectional"))
    )
    (net (code "42") (name "TEST") (class "Default")
      (node (ref "J1") (pin "P8") (pinfunction "8_P8") (pintype "bidirectional"))
      (node (ref "U3") (pin "P11") (pinfunction "TEST_P11") (pintype "bidirectional"))
    )
    (net (code "43") (name "TMS") (class "Default")
      (node (ref "J1") (pin "P5") (pinfunction "5_P5") (pintype "bidirectional"))
      (node (ref "U3") (pin "P9") (pinfunction "TMS_P9") (pintype "bidirectional"))
    )
    (net (code "44") (name "TOBLE_TX") (class "Default")
      (node (ref "SV1") (pin "P1") (pinfunction "1_P1") (pintype "passive"))
      (node (ref "U3") (pin "P13") (pinfunction "P2.0/UCATX/MOSI_P13") (pintype "bidirectional"))
      (node (ref "U4") (pin "47") (pinfunction "P28_47") (pintype "bidirectional"))
    )
    (net (code "45") (name "V+") (class "Default")
      (node (ref "C11") (pin "1") (pinfunction "1_1") (pintype "passive"))
      (node (ref "C24") (pin "1") (pinfunction "1_1") (pintype "passive"))
      (node (ref "J4") (pin "1") (pinfunction "VCC_1") (pintype "bidirectional"))
      (node (ref "Q1") (pin "P3") (pinfunction "D_P3") (pintype "passive"))
      (node (ref "U4") (pin "1") (pinfunction "VDD_1") (pintype "bidirectional"))
      (node (ref "U4") (pin "12") (pinfunction "VDD_12") (pintype "bidirectional"))
    )
    (net (code "46") (name "VAMP") (class "Default")
      (node (ref "C39") (pin "1") (pinfunction "1_1") (pintype "passive"))
      (node (ref "R17") (pin "2") (pinfunction "2_2") (pintype "passive"))
      (node (ref "U2") (pin "P4") (pinfunction "OUT_P4") (pintype "bidirectional"))
    )
    (net (code "47") (name "VCC") (class "Default")
      (node (ref "C1") (pin "+") (pinfunction "+_+") (pintype "passive"))
      (node (ref "C3") (pin "1") (pinfunction "1_1") (pintype "passive"))
      (node (ref "C7") (pin "1") (pinfunction "1_1") (pintype "passive"))
      (node (ref "C8") (pin "1") (pinfunction "1_1") (pintype "passive"))
      (node (ref "D2") (pin "C") (pinfunction "C_C") (pintype "passive"))
      (node (ref "R11") (pin "2") (pinfunction "2_2") (pintype "passive"))
      (node (ref "SV1") (pin "P10") (pinfunction "10_P10") (pintype "passive"))
      (node (ref "U1") (pin "P4") (pinfunction "EN_P4") (pintype "bidirectional"))
      (node (ref "U1") (pin "P5") (pinfunction "VIN_P5") (pintype "bidirectional"))
    )
    (net (code "48") (name "VCC_SENSE") (class "Default")
      (node (ref "R11") (pin "1") (pinfunction "1_1") (pintype "passive"))
      (node (ref "R12") (pin "2") (pinfunction "2_2") (pintype "passive"))
      (node (ref "U3") (pin "P6") (pinfunction "P1.5/TB0.2/UCACLK_P6") (pintype "bidirectional"))
    )
    (net (code "49") (name "VFILT") (class "Default")
      (node (ref "C39") (pin "2") (pinfunction "2_2") (pintype "passive"))
      (node (ref "R35") (pin "2") (pinfunction "2_2") (pintype "passive"))
      (node (ref "SV1") (pin "P9") (pinfunction "9_P9") (pintype "passive"))
      (node (ref "U3") (pin "P2") (pinfunction "P1.1/VREF+_P2") (pintype "bidirectional"))
      (node (ref "U7") (pin "P5") (pinfunction "IN+_P5") (pintype "bidirectional"))
    )
    (net (code "50") (name "VS+") (class "Default")
      (node (ref "C10") (pin "1") (pinfunction "1_1") (pintype "passive"))
      (node (ref "C4") (pin "1") (pinfunction "1_1") (pintype "passive"))
      (node (ref "C9") (pin "1") (pinfunction "1_1") (pintype "passive"))
      (node (ref "L1") (pin "1") (pinfunction "1_1") (pintype "passive"))
      (node (ref "R24") (pin "1") (pinfunction "1_1") (pintype "passive"))
      (node (ref "R7") (pin "2") (pinfunction "2_2") (pintype "passive"))
      (node (ref "SV1") (pin "P12") (pinfunction "12_P12") (pintype "passive"))
      (node (ref "U1") (pin "P2") (pinfunction "VOUT_P2") (pintype "bidirectional"))
    )
    (net (code "51") (name "VTEST") (class "Default")
      (node (ref "J2") (pin "PA.3") (pinfunction "P_PA.3") (pintype "bidirectional"))
      (node (ref "R3") (pin "1") (pinfunction "1_1") (pintype "passive"))
      (node (ref "RI1") (pin "1") (pinfunction "1_1") (pintype "passive"))
    )
    (net (code "52") (name "V_SENSE") (class "Default")
      (node (ref "RF") (pin "2") (pinfunction "2_2") (pintype "passive"))
      (node (ref "SV1") (pin "P3") (pinfunction "3_P3") (pintype "passive"))
      (node (ref "U3") (pin "P1") (pinfunction "P1.0/VREF-_P1") (pintype "bidirectional"))
      (node (ref "U6") (pin "P4") (pinfunction "OUT_P4") (pintype "bidirectional"))
    )
    (net (code "53") (name "ZC") (class "Default")
      (node (ref "D1") (pin "C") (pinfunction "C_C") (pintype "passive"))
      (node (ref "D2") (pin "A") (pinfunction "A_A") (pintype "passive"))
      (node (ref "R22") (pin "2") (pinfunction "2_2") (pintype "passive"))
      (node (ref "R3") (pin "2") (pinfunction "2_2") (pintype "passive"))
      (node (ref "SV1") (pin "P11") (pinfunction "11_P11") (pintype "passive"))
    )
    (net (code "54") (name "unconnected-(J1-4-PadP4)") (class "Default")
      (node (ref "J1") (pin "P4") (pinfunction "4_P4") (pintype "bidirectional"))
    )
    (net (code "55") (name "unconnected-(J1-6-PadP6)") (class "Default")
      (node (ref "J1") (pin "P6") (pinfunction "6_P6") (pintype "bidirectional"))
    )
    (net (code "56") (name "unconnected-(J4-SWO-Pad6)") (class "Default")
      (node (ref "J4") (pin "6") (pinfunction "SWO_6") (pintype "bidirectional"))
    )
    (net (code "57") (name "unconnected-(J4-~{RESET}-Pad3)") (class "Default")
      (node (ref "J4") (pin "3") (pinfunction "~{RESET}_3") (pintype "bidirectional"))
    )
    (net (code "58") (name "unconnected-(U4-P00{slash}AREF0-Pad4)") (class "Default")
      (node (ref "U4") (pin "4") (pinfunction "P00/AREF0_4") (pintype "bidirectional"))
    )
    (net (code "59") (name "unconnected-(U4-P01{slash}AIN2-Pad5)") (class "Default")
      (node (ref "U4") (pin "5") (pinfunction "P01/AIN2_5") (pintype "bidirectional"))
    )
    (net (code "60") (name "unconnected-(U4-P02{slash}AIN3-Pad6)") (class "Default")
      (node (ref "U4") (pin "6") (pinfunction "P02/AIN3_6") (pintype "bidirectional"))
    )
    (net (code "61") (name "unconnected-(U4-P03{slash}AIN4-Pad7)") (class "Default")
      (node (ref "U4") (pin "7") (pinfunction "P03/AIN4_7") (pintype "bidirectional"))
    )
    (net (code "62") (name "unconnected-(U4-P04{slash}AIN5-Pad8)") (class "Default")
      (node (ref "U4") (pin "8") (pinfunction "P04/AIN5_8") (pintype "bidirectional"))
    )
    (net (code "63") (name "unconnected-(U4-P06{slash}AIN7{slash}AREF1-Pad10)") (class "Default")
      (node (ref "U4") (pin "10") (pinfunction "P06/AIN7/AREF1_10") (pintype "bidirectional"))
    )
    (net (code "64") (name "unconnected-(U4-P07-Pad11)") (class "Default")
      (node (ref "U4") (pin "11") (pinfunction "P07_11") (pintype "bidirectional"))
    )
    (net (code "65") (name "unconnected-(U4-P08-Pad14)") (class "Default")
      (node (ref "U4") (pin "14") (pinfunction "P08_14") (pintype "bidirectional"))
    )
    (net (code "66") (name "unconnected-(U4-P09-Pad15)") (class "Default")
      (node (ref "U4") (pin "15") (pinfunction "P09_15") (pintype "bidirectional"))
    )
    (net (code "67") (name "unconnected-(U4-P10-Pad16)") (class "Default")
      (node (ref "U4") (pin "16") (pinfunction "P10_16") (pintype "bidirectional"))
    )
    (net (code "68") (name "unconnected-(U4-P11-Pad17)") (class "Default")
      (node (ref "U4") (pin "17") (pinfunction "P11_17") (pintype "bidirectional"))
    )
    (net (code "69") (name "unconnected-(U4-P12-Pad18)") (class "Default")
      (node (ref "U4") (pin "18") (pinfunction "P12_18") (pintype "bidirectional"))
    )
    (net (code "70") (name "unconnected-(U4-P13-Pad19)") (class "Default")
      (node (ref "U4") (pin "19") (pinfunction "P13_19") (pintype "bidirectional"))
    )
    (net (code "71") (name "unconnected-(U4-P14-Pad20)") (class "Default")
      (node (ref "U4") (pin "20") (pinfunction "P14_20") (pintype "bidirectional"))
    )
    (net (code "72") (name "unconnected-(U4-P15-Pad21)") (class "Default")
      (node (ref "U4") (pin "21") (pinfunction "P15_21") (pintype "bidirectional"))
    )
    (net (code "73") (name "unconnected-(U4-P16-Pad22)") (class "Default")
      (node (ref "U4") (pin "22") (pinfunction "P16_22") (pintype "bidirectional"))
    )
    (net (code "74") (name "unconnected-(U4-P17-Pad25)") (class "Default")
      (node (ref "U4") (pin "25") (pinfunction "P17_25") (pintype "bidirectional"))
    )
    (net (code "75") (name "unconnected-(U4-P18-Pad26)") (class "Default")
      (node (ref "U4") (pin "26") (pinfunction "P18_26") (pintype "bidirectional"))
    )
    (net (code "76") (name "unconnected-(U4-P19-Pad27)") (class "Default")
      (node (ref "U4") (pin "27") (pinfunction "P19_27") (pintype "bidirectional"))
    )
    (net (code "77") (name "unconnected-(U4-P20-Pad28)") (class "Default")
      (node (ref "U4") (pin "28") (pinfunction "P20_28") (pintype "bidirectional"))
    )
    (net (code "78") (name "unconnected-(U4-P21-Pad40)") (class "Default")
      (node (ref "U4") (pin "40") (pinfunction "P21_40") (pintype "bidirectional"))
    )
    (net (code "79") (name "unconnected-(U4-P22-Pad41)") (class "Default")
      (node (ref "U4") (pin "41") (pinfunction "P22_41") (pintype "bidirectional"))
    )
    (net (code "80") (name "unconnected-(U4-P23-Pad42)") (class "Default")
      (node (ref "U4") (pin "42") (pinfunction "P23_42") (pintype "bidirectional"))
    )
    (net (code "81") (name "unconnected-(U4-P24-Pad43)") (class "Default")
      (node (ref "U4") (pin "43") (pinfunction "P24_43") (pintype "bidirectional"))
    )
    (net (code "82") (name "unconnected-(U4-P25-Pad44)") (class "Default")
      (node (ref "U4") (pin "44") (pinfunction "P25_44") (pintype "bidirectional"))
    )
    (net (code "83") (name "unconnected-(U4-P26{slash}AIN0{slash}XL2-Pad45)") (class "Default")
      (node (ref "U4") (pin "45") (pinfunction "P26/AIN0/XL2_45") (pintype "bidirectional"))
    )
    (net (code "84") (name "unconnected-(U4-P30-Pad3)") (class "Default")
      (node (ref "U4") (pin "3") (pinfunction "P30_3") (pintype "bidirectional"))
    )
  )
)
